# N0llELAB_final.net
KiCad netlist of a schematic drawn in EAGLE
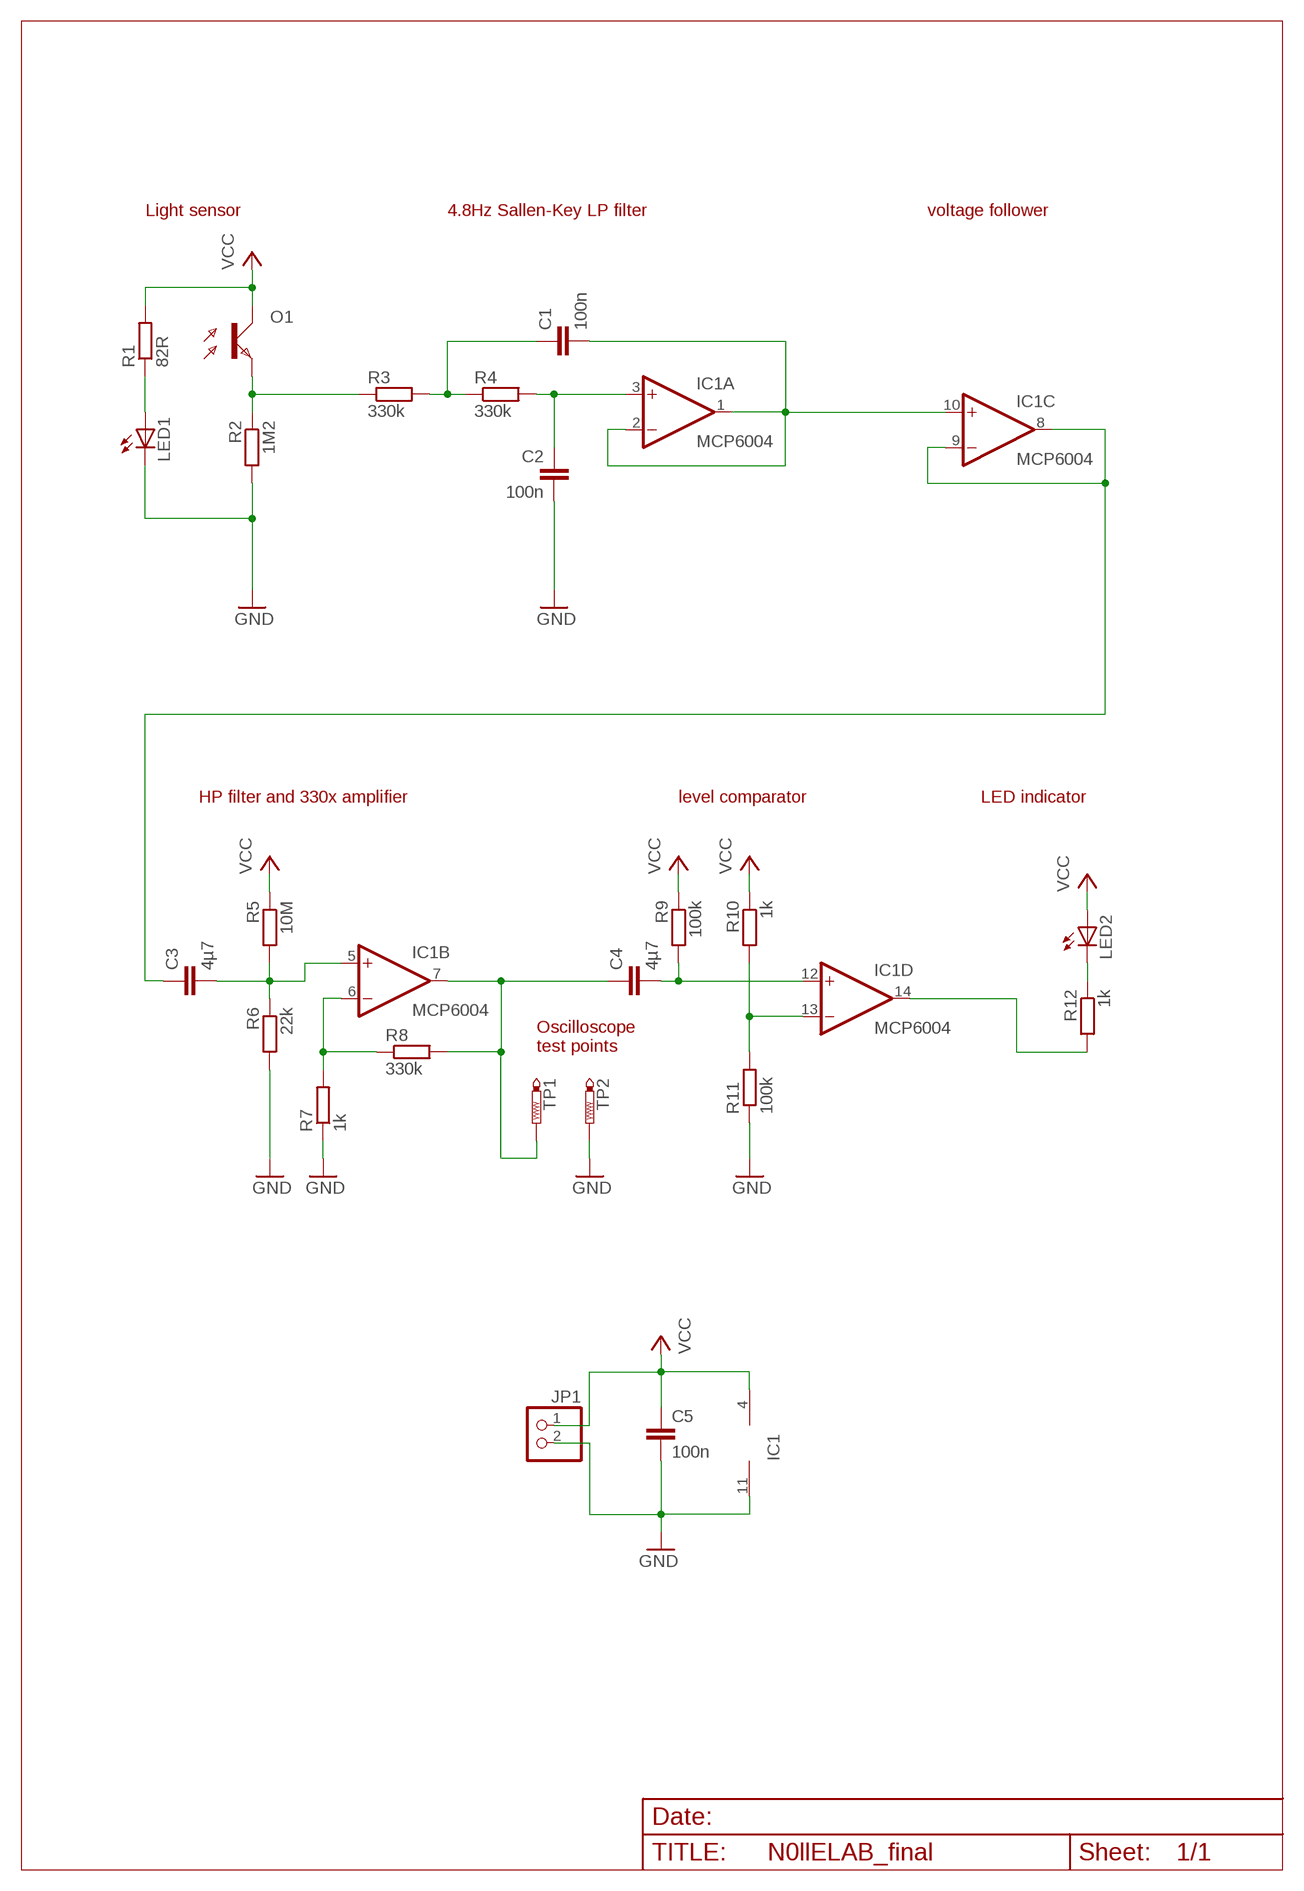
[diagram p0: schematic, sheet 1]

(export (version "E")
  (design (tool "Eeschema 10.0.6"))
  (components
    (comp (ref "C1")
      (value "100n")
      (footprint "eagle-import:C050-024X044")
      (libsource (lib "eagle-import") (part "C-EU050-024X044"))
    )
    (comp (ref "C2")
      (value "100n")
      (footprint "eagle-import:C050-024X044")
      (libsource (lib "eagle-import") (part "C-EU050-024X044"))
    )
    (comp (ref "C3")
      (value "4µ7")
      (footprint "eagle-import:C050-024X044")
      (libsource (lib "eagle-import") (part "C-EU050-024X044"))
    )
    (comp (ref "C4")
      (value "4µ7")
      (footprint "eagle-import:C050-024X044")
      (libsource (lib "eagle-import") (part "C-EU050-024X044"))
    )
    (comp (ref "C5")
      (value "100n")
      (footprint "eagle-import:C050-024X044")
      (libsource (lib "eagle-import") (part "C-EU050-024X044"))
    )
    (comp (ref "IC1")
      (value "MCP6004")
      (footprint "eagle-import:DIL14")
      (libsource (lib "eagle-import") (part "LM324N"))
    )
    (comp (ref "JP1")
      (value "PINHD-1X02_2.54-S")
      (footprint "eagle-import:1X02-S")
      (libsource (lib "eagle-import") (part "PINHD-1X02_2.54-S"))
    )
    (comp (ref "LED1")
      (value "LED5MM-90L")
      (footprint "eagle-import:LED5MM-90L")
      (libsource (lib "eagle-import") (part "LED5MM-90L"))
    )
    (comp (ref "LED2")
      (value "LED5MM")
      (footprint "eagle-import:LED5MM")
      (libsource (lib "eagle-import") (part "LED5MM"))
    )
    (comp (ref "O1")
      (value "OPTOTRANS5MM-90R")
      (footprint "eagle-import:LED5MM-90R")
      (libsource (lib "eagle-import") (part "OPTOTRANS5MM-90R"))
    )
    (comp (ref "R1")
      (value "82R")
      (footprint "eagle-import:0207_2V")
      (libsource (lib "eagle-import") (part "R-EU_0207/2V"))
    )
    (comp (ref "R2")
      (value "1M2")
      (footprint "eagle-import:0207_2V")
      (libsource (lib "eagle-import") (part "R-EU_0207/2V"))
    )
    (comp (ref "R3")
      (value "330k")
      (footprint "eagle-import:0207_2V")
      (libsource (lib "eagle-import") (part "R-EU_0207/2V"))
    )
    (comp (ref "R4")
      (value "330k")
      (footprint "eagle-import:0207_2V")
      (libsource (lib "eagle-import") (part "R-EU_0207/2V"))
    )
    (comp (ref "R5")
      (value "10M")
      (footprint "eagle-import:0207_2V")
      (libsource (lib "eagle-import") (part "R-EU_0207/2V"))
    )
    (comp (ref "R6")
      (value "22k")
      (footprint "eagle-import:0207_2V")
      (libsource (lib "eagle-import") (part "R-EU_0207/2V"))
    )
    (comp (ref "R7")
      (value "1k")
      (footprint "eagle-import:0207_2V")
      (libsource (lib "eagle-import") (part "R-EU_0207/2V"))
    )
    (comp (ref "R8")
      (value "330k")
      (footprint "eagle-import:0207_2V")
      (libsource (lib "eagle-import") (part "R-EU_0207/2V"))
    )
    (comp (ref "R9")
      (value "100k")
      (footprint "eagle-import:0207_2V")
      (libsource (lib "eagle-import") (part "R-EU_0207/2V"))
    )
    (comp (ref "R10")
      (value "1k")
      (footprint "eagle-import:0207_2V")
      (libsource (lib "eagle-import") (part "R-EU_0207/2V"))
    )
    (comp (ref "R11")
      (value "100k")
      (footprint "eagle-import:0207_2V")
      (libsource (lib "eagle-import") (part "R-EU_0207/2V"))
    )
    (comp (ref "R12")
      (value "1k")
      (footprint "eagle-import:0207_2V")
      (libsource (lib "eagle-import") (part "R-EU_0207/2V"))
    )
    (comp (ref "TP1")
      (value "PTR1PAD1-13")
      (footprint "eagle-import:P1-13")
      (libsource (lib "eagle-import") (part "PTR1PAD1-13"))
    )
    (comp (ref "TP2")
      (value "PTR1PAD1-13")
      (footprint "eagle-import:P1-13")
      (libsource (lib "eagle-import") (part "PTR1PAD1-13"))
    )
  )
  (nets
    (net (code "1") (name "GND") (class "Default")
      (node (ref "C2") (pin "2") (pinfunction "2_2") (pintype "passive"))
      (node (ref "C5") (pin "2") (pinfunction "2_2") (pintype "passive"))
      (node (ref "IC1") (pin "11") (pinfunction "V-_11") (pintype "power_in"))
      (node (ref "JP1") (pin "2") (pinfunction "2_2") (pintype "passive"))
      (node (ref "LED1") (pin "K") (pinfunction "C_K") (pintype "passive"))
      (node (ref "R11") (pin "1") (pinfunction "1_1") (pintype "passive"))
      (node (ref "R2") (pin "2") (pinfunction "2_2") (pintype "passive"))
      (node (ref "R6") (pin "2") (pinfunction "2_2") (pintype "passive"))
      (node (ref "R7") (pin "1") (pinfunction "1_1") (pintype "passive"))
      (node (ref "TP2") (pin "1") (pinfunction "TP_1") (pintype "input"))
    )
    (net (code "2") (name "Net-(C1-Pad1)") (class "Default")
      (node (ref "C1") (pin "1") (pinfunction "1_1") (pintype "passive"))
      (node (ref "R3") (pin "2") (pinfunction "2_2") (pintype "passive"))
      (node (ref "R4") (pin "1") (pinfunction "1_1") (pintype "passive"))
    )
    (net (code "3") (name "Net-(IC1A-+IN)") (class "Default")
      (node (ref "C2") (pin "1") (pinfunction "1_1") (pintype "passive"))
      (node (ref "IC1") (pin "3") (pinfunction "+IN_3") (pintype "input"))
      (node (ref "R4") (pin "2") (pinfunction "2_2") (pintype "passive"))
    )
    (net (code "4") (name "Net-(IC1A--IN)") (class "Default")
      (node (ref "C1") (pin "2") (pinfunction "2_2") (pintype "passive"))
      (node (ref "IC1") (pin "1") (pinfunction "OUT_1") (pintype "output"))
      (node (ref "IC1") (pin "10") (pinfunction "+IN_10") (pintype "input"))
      (node (ref "IC1") (pin "2") (pinfunction "-IN_2") (pintype "input"))
    )
    (net (code "5") (name "Net-(IC1B-+IN)") (class "Default")
      (node (ref "C3") (pin "2") (pinfunction "2_2") (pintype "passive"))
      (node (ref "IC1") (pin "5") (pinfunction "+IN_5") (pintype "input"))
      (node (ref "R5") (pin "2") (pinfunction "2_2") (pintype "passive"))
      (node (ref "R6") (pin "1") (pinfunction "1_1") (pintype "passive"))
    )
    (net (code "6") (name "Net-(IC1B--IN)") (class "Default")
      (node (ref "IC1") (pin "6") (pinfunction "-IN_6") (pintype "input"))
      (node (ref "R7") (pin "2") (pinfunction "2_2") (pintype "passive"))
      (node (ref "R8") (pin "1") (pinfunction "1_1") (pintype "passive"))
    )
    (net (code "7") (name "Net-(IC1B-OUT)") (class "Default")
      (node (ref "C4") (pin "1") (pinfunction "1_1") (pintype "passive"))
      (node (ref "IC1") (pin "7") (pinfunction "OUT_7") (pintype "output"))
      (node (ref "R8") (pin "2") (pinfunction "2_2") (pintype "passive"))
      (node (ref "TP1") (pin "1") (pinfunction "TP_1") (pintype "input"))
    )
    (net (code "8") (name "Net-(IC1C--IN)") (class "Default")
      (node (ref "C3") (pin "1") (pinfunction "1_1") (pintype "passive"))
      (node (ref "IC1") (pin "8") (pinfunction "OUT_8") (pintype "output"))
      (node (ref "IC1") (pin "9") (pinfunction "-IN_9") (pintype "input"))
    )
    (net (code "9") (name "Net-(IC1D-+IN)") (class "Default")
      (node (ref "C4") (pin "2") (pinfunction "2_2") (pintype "passive"))
      (node (ref "IC1") (pin "12") (pinfunction "+IN_12") (pintype "input"))
      (node (ref "R9") (pin "2") (pinfunction "2_2") (pintype "passive"))
    )
    (net (code "10") (name "Net-(IC1D--IN)") (class "Default")
      (node (ref "IC1") (pin "13") (pinfunction "-IN_13") (pintype "input"))
      (node (ref "R10") (pin "2") (pinfunction "2_2") (pintype "passive"))
      (node (ref "R11") (pin "2") (pinfunction "2_2") (pintype "passive"))
    )
    (net (code "11") (name "Net-(IC1D-OUT)") (class "Default")
      (node (ref "IC1") (pin "14") (pinfunction "OUT_14") (pintype "output"))
      (node (ref "R12") (pin "2") (pinfunction "2_2") (pintype "passive"))
    )
    (net (code "12") (name "Net-(LED1-PadA)") (class "Default")
      (node (ref "LED1") (pin "A") (pinfunction "A_A") (pintype "passive"))
      (node (ref "R1") (pin "1") (pinfunction "1_1") (pintype "passive"))
    )
    (net (code "13") (name "Net-(LED2-C)") (class "Default")
      (node (ref "LED2") (pin "K") (pinfunction "C_K") (pintype "passive"))
      (node (ref "R12") (pin "1") (pinfunction "1_1") (pintype "passive"))
    )
    (net (code "14") (name "Net-(O1-E)") (class "Default")
      (node (ref "O1") (pin "A") (pinfunction "E_A") (pintype "passive"))
      (node (ref "R2") (pin "1") (pinfunction "1_1") (pintype "passive"))
      (node (ref "R3") (pin "1") (pinfunction "1_1") (pintype "passive"))
    )
    (net (code "15") (name "VCC") (class "Default")
      (node (ref "C5") (pin "1") (pinfunction "1_1") (pintype "passive"))
      (node (ref "IC1") (pin "4") (pinfunction "V+_4") (pintype "power_in"))
      (node (ref "JP1") (pin "1") (pinfunction "1_1") (pintype "passive"))
      (node (ref "LED2") (pin "A") (pinfunction "A_A") (pintype "passive"))
      (node (ref "O1") (pin "K") (pinfunction "C_K") (pintype "passive"))
      (node (ref "R1") (pin "2") (pinfunction "2_2") (pintype "passive"))
      (node (ref "R10") (pin "1") (pinfunction "1_1") (pintype "passive"))
      (node (ref "R5") (pin "1") (pinfunction "1_1") (pintype "passive"))
      (node (ref "R9") (pin "1") (pinfunction "1_1") (pintype "passive"))
    )
  )
)
